# FourRotorV2_1.net
KiCad netlist of a schematic drawn in Altium Designer
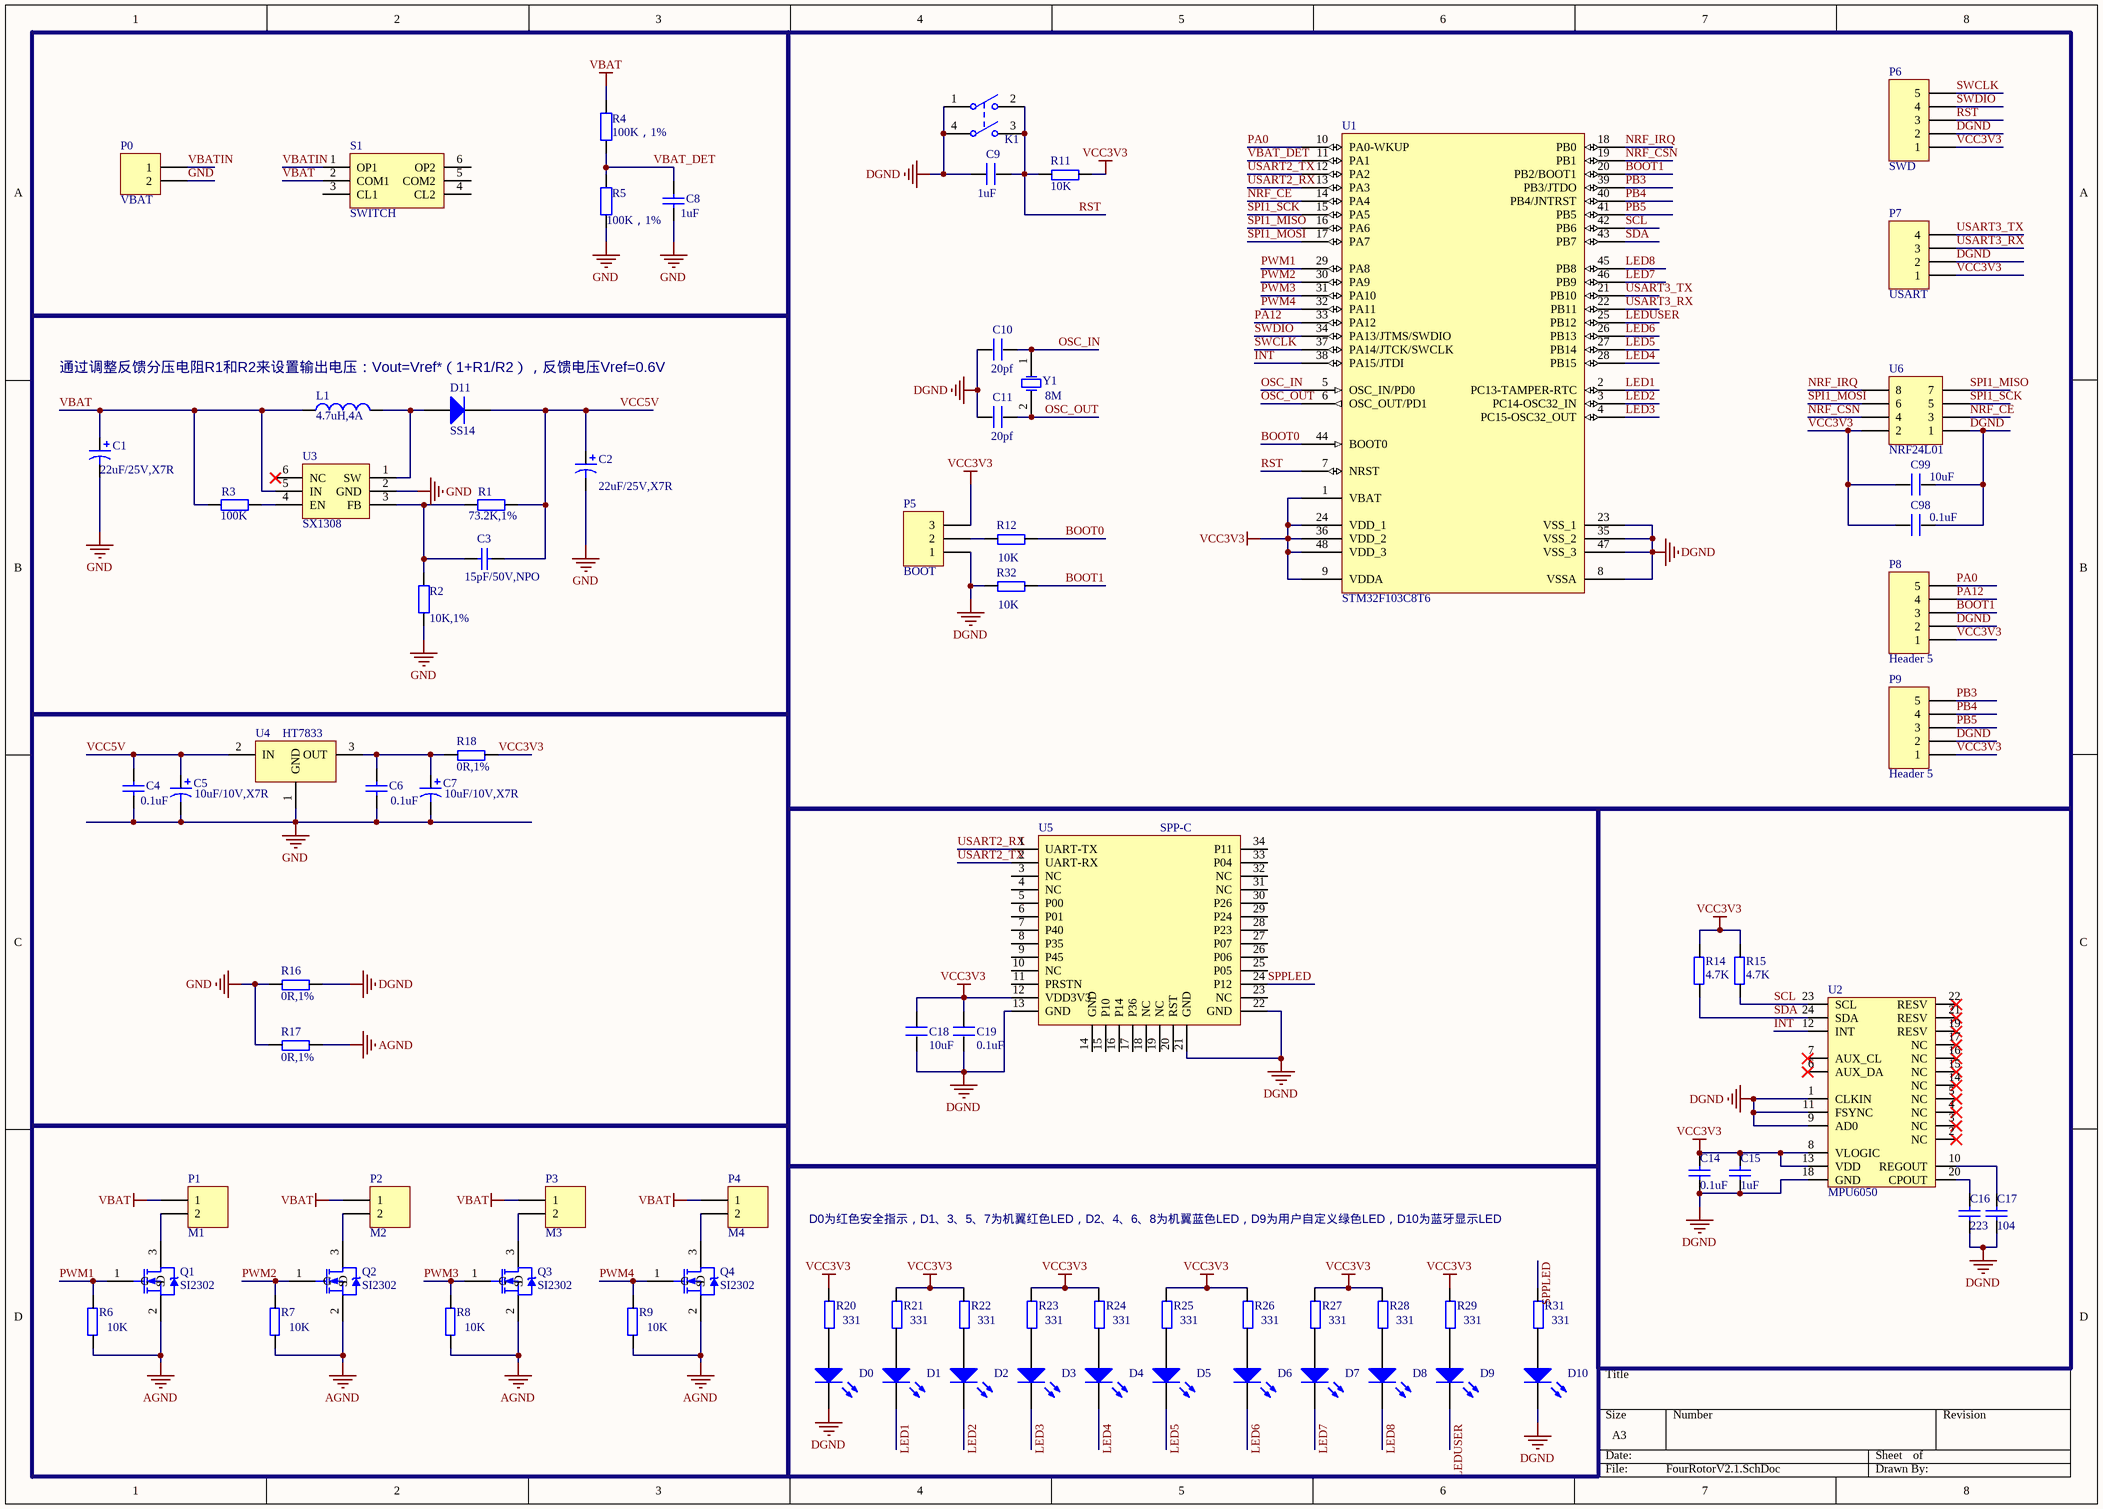
[diagram p0: FourRotorV2.1.SchDoc]

(export (version "E")
  (design (tool "Eeschema 10.0.6"))
  (components
    (comp (ref "C1")
      (value "22uF/25V,X7R")
      (footprint "LC-1206_C")
      (description "Polarized Capacitor (Radial)")
      (fields (field (name "Comment") "Cap Pol1") (field (name "PUBLISHER") "Altium Limited"))
      (libsource (lib "Miscellaneous Devices") (part "Cap Pol1"))
    )
    (comp (ref "C2")
      (value "22uF/25V,X7R")
      (footprint "LC-1206_C")
      (description "Polarized Capacitor (Radial)")
      (fields (field (name "Comment") "Cap Pol1") (field (name "PUBLISHER") "Altium Limited"))
      (libsource (lib "Miscellaneous Devices") (part "Cap Pol1"))
    )
    (comp (ref "C3")
      (value "15pF/50V,NPO")
      (footprint "LC-0603_C")
      (description "Capacitor")
      (fields (field (name "Comment") "Cap") (field (name "PUBLISHER") "Altium Limited"))
      (libsource (lib "Miscellaneous Devices") (part "Cap"))
    )
    (comp (ref "C4")
      (value "0.1uF")
      (footprint "LC-0603_C")
      (description "Capacitor")
      (fields (field (name "Comment") "Cap") (field (name "PUBLISHER") "Altium Limited"))
      (libsource (lib "Miscellaneous Devices") (part "Cap"))
    )
    (comp (ref "C5")
      (value "10uF/10V,X7R")
      (footprint "LC-1206_C")
      (description "Polarized Capacitor (Radial)")
      (fields (field (name "Comment") "Cap Pol1") (field (name "PUBLISHER") "Altium Limited"))
      (libsource (lib "Miscellaneous Devices") (part "Cap Pol1"))
    )
    (comp (ref "C6")
      (value "0.1uF")
      (footprint "LC-0603_C")
      (description "Capacitor")
      (fields (field (name "Comment") "Cap") (field (name "PUBLISHER") "Altium Limited"))
      (libsource (lib "Miscellaneous Devices") (part "Cap"))
    )
    (comp (ref "C7")
      (value "10uF/10V,X7R")
      (footprint "LC-1206_C")
      (description "Polarized Capacitor (Radial)")
      (fields (field (name "Comment") "Cap Pol1") (field (name "PUBLISHER") "Altium Limited"))
      (libsource (lib "Miscellaneous Devices") (part "Cap Pol1"))
    )
    (comp (ref "C8")
      (value "1uF")
      (footprint "LC-0603_C")
      (description "Capacitor")
      (fields (field (name "Comment") "Cap") (field (name "PUBLISHER") "Altium Limited"))
      (libsource (lib "Miscellaneous Devices") (part "Cap"))
    )
    (comp (ref "C9")
      (value "1uF")
      (footprint "LC-0603_C")
      (libsource (lib "Explorer STM32F407封装库") (part "C_1"))
    )
    (comp (ref "C10")
      (value "20pf")
      (footprint "LC-0603_C")
      (libsource (lib "Explorer STM32F407封装库") (part "C"))
    )
    (comp (ref "C11")
      (value "20pf")
      (footprint "LC-0603_C")
      (libsource (lib "Explorer STM32F407封装库") (part "C"))
    )
    (comp (ref "C14")
      (value "0.1uF")
      (footprint "LC-0603_C")
      (description "Capacitor")
      (fields (field (name "PUBLISHER") "Altium Limited"))
      (libsource (lib "Miscellaneous Devices") (part "Cap"))
    )
    (comp (ref "C15")
      (value "1uF")
      (footprint "LC-0603_C")
      (description "Capacitor")
      (fields (field (name "PUBLISHER") "Altium Limited"))
      (libsource (lib "Miscellaneous Devices") (part "Cap"))
    )
    (comp (ref "C16")
      (value "223")
      (footprint "LC-0603_C")
      (description "Capacitor")
      (fields (field (name "PUBLISHER") "Altium Limited"))
      (libsource (lib "Miscellaneous Devices") (part "Cap"))
    )
    (comp (ref "C17")
      (value "104")
      (footprint "LC-0603_C")
      (description "Capacitor")
      (fields (field (name "PUBLISHER") "Altium Limited"))
      (libsource (lib "Miscellaneous Devices") (part "Cap"))
    )
    (comp (ref "C18")
      (value "10uF")
      (footprint "LC-0805_C")
      (libsource (lib "Explorer STM32F407封装库") (part "C"))
    )
    (comp (ref "C19")
      (value "0.1uF")
      (footprint "LC-0603_C")
      (libsource (lib "Explorer STM32F407封装库") (part "C"))
    )
    (comp (ref "C98")
      (value "0.1uF")
      (footprint "LC-0603_C")
      (fields (field (name "Comment") "1uF"))
      (libsource (lib "Explorer STM32F407封装库") (part "C_1"))
    )
    (comp (ref "C99")
      (value "10uF")
      (footprint "LC-0805_C")
      (fields (field (name "Comment") "1uF"))
      (libsource (lib "Explorer STM32F407封装库") (part "C_1"))
    )
    (comp (ref "D0")
      (value "LED0")
      (footprint "LC-0805_LED_S1")
      (description "Typical INFRARED GaAs LED")
      (fields (field (name "PUBLISHER") "Altium Limited"))
      (libsource (lib "Miscellaneous Devices") (part "LED0"))
    )
    (comp (ref "D1")
      (value "LED0")
      (footprint "LC-0805_LED_S1")
      (description "Typical INFRARED GaAs LED")
      (fields (field (name "PUBLISHER") "Altium Limited"))
      (libsource (lib "Miscellaneous Devices") (part "LED0"))
    )
    (comp (ref "D2")
      (value "LED0")
      (footprint "LC-0805_LED_S1")
      (description "Typical INFRARED GaAs LED")
      (fields (field (name "PUBLISHER") "Altium Limited"))
      (libsource (lib "Miscellaneous Devices") (part "LED0"))
    )
    (comp (ref "D3")
      (value "LED0")
      (footprint "LC-0805_LED_S1")
      (description "Typical INFRARED GaAs LED")
      (fields (field (name "PUBLISHER") "Altium Limited"))
      (libsource (lib "Miscellaneous Devices") (part "LED0"))
    )
    (comp (ref "D4")
      (value "LED0")
      (footprint "LC-0805_LED_S1")
      (description "Typical INFRARED GaAs LED")
      (fields (field (name "PUBLISHER") "Altium Limited"))
      (libsource (lib "Miscellaneous Devices") (part "LED0"))
    )
    (comp (ref "D5")
      (value "LED0")
      (footprint "LC-0805_LED_S1")
      (description "Typical INFRARED GaAs LED")
      (fields (field (name "PUBLISHER") "Altium Limited"))
      (libsource (lib "Miscellaneous Devices") (part "LED0"))
    )
    (comp (ref "D6")
      (value "LED0")
      (footprint "LC-0805_LED_S1")
      (description "Typical INFRARED GaAs LED")
      (fields (field (name "PUBLISHER") "Altium Limited"))
      (libsource (lib "Miscellaneous Devices") (part "LED0"))
    )
    (comp (ref "D7")
      (value "LED0")
      (footprint "LC-0805_LED_S1")
      (description "Typical INFRARED GaAs LED")
      (fields (field (name "PUBLISHER") "Altium Limited"))
      (libsource (lib "Miscellaneous Devices") (part "LED0"))
    )
    (comp (ref "D8")
      (value "LED0")
      (footprint "LC-0805_LED_S1")
      (description "Typical INFRARED GaAs LED")
      (fields (field (name "PUBLISHER") "Altium Limited"))
      (libsource (lib "Miscellaneous Devices") (part "LED0"))
    )
    (comp (ref "D9")
      (value "LED0")
      (footprint "LC-0805_LED_S1")
      (description "Typical INFRARED GaAs LED")
      (fields (field (name "PUBLISHER") "Altium Limited"))
      (libsource (lib "Miscellaneous Devices") (part "LED0"))
    )
    (comp (ref "D10")
      (value "LED0")
      (footprint "LC-0805_LED_S1")
      (description "Typical INFRARED GaAs LED")
      (fields (field (name "PUBLISHER") "Altium Limited"))
      (libsource (lib "Miscellaneous Devices") (part "LED0"))
    )
    (comp (ref "D11")
      (value "SS14")
      (footprint "LC-DO-214AC")
      (description "1 Amp General Purpose Rectifier")
      (fields (field (name "PUBLISHER") "Altium Limited"))
      (libsource (lib "Miscellaneous Devices") (part "Diode 1N4001"))
    )
    (comp (ref "K1")
      (value "SW-DPST")
      (footprint "SWITCH2")
      (description "Double-Pole, Single-Throw Switch")
      (fields (field (name "PUBLISHER") "Altium Limited"))
      (libsource (lib "Miscellaneous Devices") (part "SW-DPST"))
    )
    (comp (ref "L1")
      (value "4.7uH,4A")
      (footprint "LC-1812_L")
      (description "Inductor")
      (fields (field (name "PUBLISHER") "Altium Limited"))
      (libsource (lib "Miscellaneous Devices") (part "Inductor"))
    )
    (comp (ref "P0")
      (value "VBAT")
      (footprint "HDR1X2")
      (description "Header, 2-Pin")
      (fields (field (name "PUBLISHER") "Altium Limited"))
      (libsource (lib "") (part "Header 2_1"))
    )
    (comp (ref "P1")
      (value "M1")
      (footprint "HDR1X2")
      (description "Header, 2-Pin")
      (fields (field (name "PUBLISHER") "Altium Limited"))
      (libsource (lib "Miscellaneous Connectors") (part "Header 2"))
    )
    (comp (ref "P2")
      (value "M2")
      (footprint "HDR1X2")
      (description "Header, 2-Pin")
      (fields (field (name "PUBLISHER") "Altium Limited"))
      (libsource (lib "Miscellaneous Connectors") (part "Header 2"))
    )
    (comp (ref "P3")
      (value "M3")
      (footprint "HDR1X2")
      (description "Header, 2-Pin")
      (fields (field (name "PUBLISHER") "Altium Limited"))
      (libsource (lib "Miscellaneous Connectors") (part "Header 2"))
    )
    (comp (ref "P4")
      (value "M4")
      (footprint "HDR1X2")
      (description "Header, 2-Pin")
      (fields (field (name "PUBLISHER") "Altium Limited"))
      (libsource (lib "Miscellaneous Connectors") (part "Header 2"))
    )
    (comp (ref "P5")
      (value "BOOT")
      (footprint "HDR1X3")
      (description "Header, 3-Pin")
      (fields (field (name "PUBLISHER") "Altium Limited"))
      (libsource (lib "Miscellaneous Connectors") (part "Header 3"))
    )
    (comp (ref "P6")
      (value "SWD")
      (footprint "HDR1X5")
      (description "Header, 5-Pin")
      (fields (field (name "PUBLISHER") "Altium Limited"))
      (libsource (lib "Miscellaneous Connectors") (part "Header 5"))
    )
    (comp (ref "P7")
      (value "USART")
      (footprint "HDR1X4")
      (description "Header, 4-Pin")
      (fields (field (name "PUBLISHER") "Altium Limited"))
      (libsource (lib "Miscellaneous Connectors") (part "Header 4"))
    )
    (comp (ref "P8")
      (value "Header 5")
      (footprint "HDR1X5")
      (description "Header, 5-Pin")
      (fields (field (name "PUBLISHER") "Altium Limited"))
      (libsource (lib "Miscellaneous Connectors") (part "Header 5"))
    )
    (comp (ref "P9")
      (value "Header 5")
      (footprint "HDR1X5")
      (description "Header, 5-Pin")
      (fields (field (name "PUBLISHER") "Altium Limited"))
      (libsource (lib "Miscellaneous Connectors") (part "Header 5"))
    )
    (comp (ref "Q1")
      (value "SI2302")
      (footprint "LC-SOT-23(SOT-23-3)")
      (description "N-Channel Power MOSFET")
      (fields (field (name "PUBLISHER") "Altium Limited"))
      (libsource (lib "Miscellaneous Devices") (part "NMOS-2"))
    )
    (comp (ref "Q2")
      (value "SI2302")
      (footprint "LC-SOT-23(SOT-23-3)")
      (description "N-Channel Power MOSFET")
      (fields (field (name "PUBLISHER") "Altium Limited"))
      (libsource (lib "Miscellaneous Devices") (part "NMOS-2"))
    )
    (comp (ref "Q3")
      (value "SI2302")
      (footprint "LC-SOT-23(SOT-23-3)")
      (description "N-Channel Power MOSFET")
      (fields (field (name "PUBLISHER") "Altium Limited"))
      (libsource (lib "Miscellaneous Devices") (part "NMOS-2"))
    )
    (comp (ref "Q4")
      (value "SI2302")
      (footprint "LC-SOT-23(SOT-23-3)")
      (description "N-Channel Power MOSFET")
      (fields (field (name "PUBLISHER") "Altium Limited"))
      (libsource (lib "Miscellaneous Devices") (part "NMOS-2"))
    )
    (comp (ref "R1")
      (value "73.2K,1%")
      (footprint "LC-0603_R")
      (description "Resistor")
      (fields (field (name "Comment") "Res2") (field (name "PUBLISHER") "Altium Limited"))
      (libsource (lib "Miscellaneous Devices") (part "Res2"))
    )
    (comp (ref "R2")
      (value "10K,1%")
      (footprint "LC-0603_R")
      (description "Resistor")
      (fields (field (name "Comment") "Res2") (field (name "PUBLISHER") "Altium Limited"))
      (libsource (lib "") (part "Res2_1"))
    )
    (comp (ref "R3")
      (value "100K")
      (footprint "LC-0603_R")
      (description "Resistor")
      (fields (field (name "Comment") "Res2") (field (name "PUBLISHER") "Altium Limited"))
      (libsource (lib "Miscellaneous Devices") (part "Res2"))
    )
    (comp (ref "R4")
      (value "100K，1%")
      (footprint "LC-0603_R")
      (description "Resistor")
      (fields (field (name "Comment") "Res2") (field (name "PUBLISHER") "Altium Limited"))
      (libsource (lib "") (part "Res2_1"))
    )
    (comp (ref "R5")
      (value "100K，1%")
      (footprint "LC-0603_R")
      (description "Resistor")
      (fields (field (name "Comment") "Res2") (field (name "PUBLISHER") "Altium Limited"))
      (libsource (lib "") (part "Res2_1"))
    )
    (comp (ref "R6")
      (value "10K")
      (footprint "LC-0603_R")
      (libsource (lib "Explorer STM32F407封装库") (part "R"))
    )
    (comp (ref "R7")
      (value "10K")
      (footprint "LC-0603_R")
      (libsource (lib "Explorer STM32F407封装库") (part "R"))
    )
    (comp (ref "R8")
      (value "10K")
      (footprint "LC-0603_R")
      (libsource (lib "Explorer STM32F407封装库") (part "R"))
    )
    (comp (ref "R9")
      (value "10K")
      (footprint "LC-0603_R")
      (libsource (lib "Explorer STM32F407封装库") (part "R"))
    )
    (comp (ref "R11")
      (value "10K")
      (footprint "LC-0603_R")
      (libsource (lib "Explorer STM32F407封装库") (part "R_1"))
    )
    (comp (ref "R12")
      (value "10K")
      (footprint "LC-0603_R")
      (libsource (lib "Explorer STM32F407封装库") (part "R"))
    )
    (comp (ref "R14")
      (value "4.7K")
      (footprint "LC-0603_R")
      (libsource (lib "Explorer STM32F407封装库") (part "R_1"))
    )
    (comp (ref "R15")
      (value "4.7K")
      (footprint "LC-0603_R")
      (libsource (lib "Explorer STM32F407封装库") (part "R_1"))
    )
    (comp (ref "R16")
      (value "0R,1%")
      (footprint "LC-0805_R")
      (libsource (lib "Explorer STM32F407封装库") (part "R"))
    )
    (comp (ref "R17")
      (value "0R,1%")
      (footprint "LC-0805_R")
      (libsource (lib "Explorer STM32F407封装库") (part "R"))
    )
    (comp (ref "R18")
      (value "0R,1%")
      (footprint "LC-0805_R")
      (libsource (lib "Explorer STM32F407封装库") (part "R"))
    )
    (comp (ref "R20")
      (value "331")
      (footprint "LC-0603_R")
      (libsource (lib "Explorer STM32F407封装库") (part "R_1"))
    )
    (comp (ref "R21")
      (value "331")
      (footprint "LC-0603_R")
      (libsource (lib "Explorer STM32F407封装库") (part "R_1"))
    )
    (comp (ref "R22")
      (value "331")
      (footprint "LC-0603_R")
      (libsource (lib "Explorer STM32F407封装库") (part "R_1"))
    )
    (comp (ref "R23")
      (value "331")
      (footprint "LC-0603_R")
      (libsource (lib "Explorer STM32F407封装库") (part "R_1"))
    )
    (comp (ref "R24")
      (value "331")
      (footprint "LC-0603_R")
      (libsource (lib "Explorer STM32F407封装库") (part "R_1"))
    )
    (comp (ref "R25")
      (value "331")
      (footprint "LC-0603_R")
      (libsource (lib "Explorer STM32F407封装库") (part "R_1"))
    )
    (comp (ref "R26")
      (value "331")
      (footprint "LC-0603_R")
      (libsource (lib "Explorer STM32F407封装库") (part "R_1"))
    )
    (comp (ref "R27")
      (value "331")
      (footprint "LC-0603_R")
      (libsource (lib "Explorer STM32F407封装库") (part "R_1"))
    )
    (comp (ref "R28")
      (value "331")
      (footprint "LC-0603_R")
      (libsource (lib "Explorer STM32F407封装库") (part "R_1"))
    )
    (comp (ref "R29")
      (value "331")
      (footprint "LC-0603_R")
      (libsource (lib "Explorer STM32F407封装库") (part "R_1"))
    )
    (comp (ref "R31")
      (value "331")
      (footprint "LC-0603_R")
      (libsource (lib "Explorer STM32F407封装库") (part "R_1"))
    )
    (comp (ref "R32")
      (value "10K")
      (footprint "LC-0603_R")
      (libsource (lib "Explorer STM32F407封装库") (part "R"))
    )
    (comp (ref "S1") (value "SWITCH") (footprint "SWITCH_6") (libsource (lib "mzwlib") (part "SWITCH")))
    (comp (ref "U1")
      (value "STM32F103C8T6")
      (footprint "LC-LQFP-48_7x7x05P")
      (description "STM32 ARM-based 32-bit MCU with 64 Kbytes Flash, 48-pin LQFP, Industrial Temperature")
      (fields (field (name "PUBLISHER") "Altium Limited"))
      (libsource (lib "ST Microcontroller 32-Bit STM32") (part "STM32F103C8T6"))
    )
    (comp (ref "U2")
      (value "MPU6050")
      (footprint "LC-QFN-24_4x4x05P")
      (description "9轴运动处理传感器")
      (libsource (lib "Explorer STM32F407封装库") (part "MPU6050"))
    )
    (comp (ref "U3") (value "SX1308") (footprint "LC-SOT-23-6") (libsource (lib "mzwlib") (part "SX1308")))
    (comp (ref "U4")
      (value "HT7833")
      (footprint "LC-SOT-89(SOT-89-3)")
      (libsource (lib "mzwlib") (part "HT7833"))
    )
    (comp (ref "U5") (value "SPP-C") (footprint "SPP-C") (libsource (lib "mzwlib") (part "SPP-C")))
    (comp (ref "U6")
      (value "NRF24L01")
      (footprint "LC-HDR2X4H")
      (description "Header, 4-Pin, Dual row, Right Angle")
      (fields (field (name "PUBLISHER") "Altium Limited"))
      (libsource (lib "Miscellaneous Connectors") (part "Header 4X2H"))
    )
    (comp (ref "Y1")
      (value "~")
      (footprint "LC-HC-49S")
      (description "Crystal Oscillator")
      (fields (field (name "ALTIUM_UNNAMED_1") "8M") (field (name "PUBLISHER") "Altium Limited"))
      (libsource (lib "Explorer STM32F407封装库") (part "XTAL"))
    )
  )
  (nets
    (net (code "1") (name "/BOOT0") (class "Default")
      (node (ref "R12") (pin "2") (pintype "passive"))
      (node (ref "U1") (pin "44") (pinfunction "BOOT0_44") (pintype "input"))
    )
    (net (code "2") (name "/BOOT1") (class "Default")
      (node (ref "P8") (pin "3") (pinfunction "3_3") (pintype "passive"))
      (node (ref "R32") (pin "2") (pintype "passive"))
      (node (ref "U1") (pin "20") (pinfunction "PB2/BOOT1_20") (pintype "bidirectional"))
    )
    (net (code "3") (name "/INT") (class "Default")
      (node (ref "U1") (pin "38") (pinfunction "PA15/JTDI_38") (pintype "bidirectional"))
      (node (ref "U2") (pin "12") (pinfunction "INT_12") (pintype "passive"))
    )
    (net (code "4") (name "/LED1") (class "Default")
      (node (ref "D1") (pin "2") (pinfunction "K_2") (pintype "passive"))
      (node (ref "U1") (pin "2") (pinfunction "PC13-TAMPER-RTC_2") (pintype "bidirectional"))
    )
    (net (code "5") (name "/LED2") (class "Default")
      (node (ref "D2") (pin "2") (pinfunction "K_2") (pintype "passive"))
      (node (ref "U1") (pin "3") (pinfunction "PC14-OSC32_IN_3") (pintype "bidirectional"))
    )
    (net (code "6") (name "/LED3") (class "Default")
      (node (ref "D3") (pin "2") (pinfunction "K_2") (pintype "passive"))
      (node (ref "U1") (pin "4") (pinfunction "PC15-OSC32_OUT_4") (pintype "bidirectional"))
    )
    (net (code "7") (name "/LED4") (class "Default")
      (node (ref "D4") (pin "2") (pinfunction "K_2") (pintype "passive"))
      (node (ref "U1") (pin "28") (pinfunction "PB15_28") (pintype "bidirectional"))
    )
    (net (code "8") (name "/LED5") (class "Default")
      (node (ref "D5") (pin "2") (pinfunction "K_2") (pintype "passive"))
      (node (ref "U1") (pin "27") (pinfunction "PB14_27") (pintype "bidirectional"))
    )
    (net (code "9") (name "/LED6") (class "Default")
      (node (ref "D6") (pin "2") (pinfunction "K_2") (pintype "passive"))
      (node (ref "U1") (pin "26") (pinfunction "PB13_26") (pintype "bidirectional"))
    )
    (net (code "10") (name "/LED7") (class "Default")
      (node (ref "D7") (pin "2") (pinfunction "K_2") (pintype "passive"))
      (node (ref "U1") (pin "46") (pinfunction "PB9_46") (pintype "bidirectional"))
    )
    (net (code "11") (name "/LED8") (class "Default")
      (node (ref "D8") (pin "2") (pinfunction "K_2") (pintype "passive"))
      (node (ref "U1") (pin "45") (pinfunction "PB8_45") (pintype "bidirectional"))
    )
    (net (code "12") (name "/LEDUSER") (class "Default")
      (node (ref "D9") (pin "2") (pinfunction "K_2") (pintype "passive"))
      (node (ref "U1") (pin "25") (pinfunction "PB12_25") (pintype "bidirectional"))
    )
    (net (code "13") (name "/NRF_CE") (class "Default")
      (node (ref "U1") (pin "14") (pinfunction "PA4_14") (pintype "bidirectional"))
      (node (ref "U6") (pin "3") (pinfunction "3_3") (pintype "passive"))
    )
    (net (code "14") (name "/NRF_CSN") (class "Default")
      (node (ref "U1") (pin "19") (pinfunction "PB1_19") (pintype "bidirectional"))
      (node (ref "U6") (pin "4") (pinfunction "4_4") (pintype "passive"))
    )
    (net (code "15") (name "/NRF_IRQ") (class "Default")
      (node (ref "U1") (pin "18") (pinfunction "PB0_18") (pintype "bidirectional"))
      (node (ref "U6") (pin "8") (pinfunction "8_8") (pintype "passive"))
    )
    (net (code "16") (name "/OSC_IN") (class "Default")
      (node (ref "C10") (pin "2") (pintype "passive"))
      (node (ref "U1") (pin "5") (pinfunction "OSC_IN/PD0_5") (pintype "input"))
      (node (ref "Y1") (pin "1") (pinfunction "OSC1_1") (pintype "passive"))
    )
    (net (code "17") (name "/OSC_OUT") (class "Default")
      (node (ref "C11") (pin "2") (pintype "passive"))
      (node (ref "U1") (pin "6") (pinfunction "OSC_OUT/PD1_6") (pintype "output"))
      (node (ref "Y1") (pin "2") (pinfunction "OSC2_2") (pintype "passive"))
    )
    (net (code "18") (name "/PA0") (class "Default")
      (node (ref "P8") (pin "5") (pinfunction "5_5") (pintype "passive"))
      (node (ref "U1") (pin "10") (pinfunction "PA0-WKUP_10") (pintype "bidirectional"))
    )
    (net (code "19") (name "/PA12") (class "Default")
      (node (ref "P8") (pin "4") (pinfunction "4_4") (pintype "passive"))
      (node (ref "U1") (pin "33") (pinfunction "PA12_33") (pintype "bidirectional"))
    )
    (net (code "20") (name "/PB3") (class "Default")
      (node (ref "P9") (pin "5") (pinfunction "5_5") (pintype "passive"))
      (node (ref "U1") (pin "39") (pinfunction "PB3/JTDO_39") (pintype "bidirectional"))
    )
    (net (code "21") (name "/PB4") (class "Default")
      (node (ref "P9") (pin "4") (pinfunction "4_4") (pintype "passive"))
      (node (ref "U1") (pin "40") (pinfunction "PB4/JNTRST_40") (pintype "bidirectional"))
    )
    (net (code "22") (name "/PB5") (class "Default")
      (node (ref "P9") (pin "3") (pinfunction "3_3") (pintype "passive"))
      (node (ref "U1") (pin "41") (pinfunction "PB5_41") (pintype "bidirectional"))
    )
    (net (code "23") (name "/PWM1") (class "Default")
      (node (ref "Q1") (pin "1") (pinfunction "G_1") (pintype "passive"))
      (node (ref "R6") (pin "1") (pintype "passive"))
      (node (ref "U1") (pin "29") (pinfunction "PA8_29") (pintype "bidirectional"))
    )
    (net (code "24") (name "/PWM2") (class "Default")
      (node (ref "Q2") (pin "1") (pinfunction "G_1") (pintype "passive"))
      (node (ref "R7") (pin "1") (pintype "passive"))
      (node (ref "U1") (pin "30") (pinfunction "PA9_30") (pintype "bidirectional"))
    )
    (net (code "25") (name "/PWM3") (class "Default")
      (node (ref "Q3") (pin "1") (pinfunction "G_1") (pintype "passive"))
      (node (ref "R8") (pin "1") (pintype "passive"))
      (node (ref "U1") (pin "31") (pinfunction "PA10_31") (pintype "bidirectional"))
    )
    (net (code "26") (name "/PWM4") (class "Default")
      (node (ref "Q4") (pin "1") (pinfunction "G_1") (pintype "passive"))
      (node (ref "R9") (pin "1") (pintype "passive"))
      (node (ref "U1") (pin "32") (pinfunction "PA11_32") (pintype "bidirectional"))
    )
    (net (code "27") (name "/RST") (class "Default")
      (node (ref "C9") (pin "2") (pintype "passive"))
      (node (ref "K1") (pin "2") (pinfunction "NO1_2") (pintype "passive"))
      (node (ref "K1") (pin "3") (pinfunction "NO2_3") (pintype "passive"))
      (node (ref "P6") (pin "3") (pinfunction "3_3") (pintype "passive"))
      (node (ref "R11") (pin "1") (pintype "passive"))
      (node (ref "U1") (pin "7") (pinfunction "NRST_7") (pintype "bidirectional"))
    )
    (net (code "28") (name "/SCL") (class "Default")
      (node (ref "R15") (pin "2") (pintype "passive"))
      (node (ref "U1") (pin "42") (pinfunction "PB6_42") (pintype "bidirectional"))
      (node (ref "U2") (pin "23") (pinfunction "SCL_23") (pintype "passive"))
    )
    (net (code "29") (name "/SDA") (class "Default")
      (node (ref "R14") (pin "2") (pintype "passive"))
      (node (ref "U1") (pin "43") (pinfunction "PB7_43") (pintype "bidirectional"))
      (node (ref "U2") (pin "24") (pinfunction "SDA_24") (pintype "passive"))
    )
    (net (code "30") (name "/SPI1_MISO") (class "Default")
      (node (ref "U1") (pin "16") (pinfunction "PA6_16") (pintype "bidirectional"))
      (node (ref "U6") (pin "7") (pinfunction "7_7") (pintype "passive"))
    )
    (net (code "31") (name "/SPI1_MOSI") (class "Default")
      (node (ref "U1") (pin "17") (pinfunction "PA7_17") (pintype "bidirectional"))
      (node (ref "U6") (pin "6") (pinfunction "6_6") (pintype "passive"))
    )
    (net (code "32") (name "/SPI1_SCK") (class "Default")
      (node (ref "U1") (pin "15") (pinfunction "PA5_15") (pintype "bidirectional"))
      (node (ref "U6") (pin "5") (pinfunction "5_5") (pintype "passive"))
    )
    (net (code "33") (name "/SPPLED") (class "Default")
      (node (ref "R31") (pin "2") (pintype "passive"))
      (node (ref "U5") (pin "24") (pinfunction "P12_24") (pintype "passive"))
    )
    (net (code "34") (name "/SWCLK") (class "Default")
      (node (ref "P6") (pin "5") (pinfunction "5_5") (pintype "passive"))
      (node (ref "U1") (pin "37") (pinfunction "PA14/JTCK/SWCLK_37") (pintype "bidirectional"))
    )
    (net (code "35") (name "/SWDIO") (class "Default")
      (node (ref "P6") (pin "4") (pinfunction "4_4") (pintype "passive"))
      (node (ref "U1") (pin "34") (pinfunction "PA13/JTMS/SWDIO_34") (pintype "bidirectional"))
    )
    (net (code "36") (name "/USART2_RX") (class "Default")
      (node (ref "U1") (pin "13") (pinfunction "PA3_13") (pintype "bidirectional"))
      (node (ref "U5") (pin "1") (pinfunction "UART-TX_1") (pintype "passive"))
    )
    (net (code "37") (name "/USART2_TX") (class "Default")
      (node (ref "U1") (pin "12") (pinfunction "PA2_12") (pintype "bidirectional"))
      (node (ref "U5") (pin "2") (pinfunction "UART-RX_2") (pintype "passive"))
    )
    (net (code "38") (name "/USART3_RX") (class "Default")
      (node (ref "P7") (pin "3") (pinfunction "3_3") (pintype "passive"))
      (node (ref "U1") (pin "22") (pinfunction "PB11_22") (pintype "bidirectional"))
    )
    (net (code "39") (name "/USART3_TX") (class "Default")
      (node (ref "P7") (pin "4") (pinfunction "4_4") (pintype "passive"))
      (node (ref "U1") (pin "21") (pinfunction "PB10_21") (pintype "bidirectional"))
    )
    (net (code "40") (name "/VBATIN") (class "Default")
      (node (ref "P0") (pin "1") (pinfunction "1_1") (pintype "passive"))
      (node (ref "S1") (pin "1") (pinfunction "OP1_1") (pintype "passive"))
    )
    (net (code "41") (name "/VBAT_DET") (class "Default")
      (node (ref "C8") (pin "2") (pinfunction "2_2") (pintype "passive"))
      (node (ref "R4") (pin "1") (pinfunction "1_1") (pintype "passive"))
      (node (ref "R5") (pin "2") (pinfunction "2_2") (pintype "passive"))
      (node (ref "U1") (pin "11") (pinfunction "PA1_11") (pintype "bidirectional"))
    )
    (net (code "42") (name "/VCC5V") (class "Default")
      (node (ref "C2") (pin "1") (pinfunction "1_1") (pintype "passive"))
      (node (ref "C3") (pin "2") (pinfunction "2_2") (pintype "passive"))
      (node (ref "C4") (pin "2") (pinfunction "2_2") (pintype "passive"))
      (node (ref "C5") (pin "1") (pinfunction "1_1") (pintype "passive"))
      (node (ref "D11") (pin "2") (pinfunction "K_2") (pintype "passive"))
      (node (ref "R1") (pin "2") (pinfunction "2_2") (pintype "passive"))
      (node (ref "U4") (pin "2") (pinfunction "IN_2") (pintype "passive"))
    )
    (net (code "43") (name "AGND") (class "Default")
      (node (ref "Q1") (pin "2") (pinfunction "S_2") (pintype "passive"))
      (node (ref "Q2") (pin "2") (pinfunction "S_2") (pintype "passive"))
      (node (ref "Q3") (pin "2") (pinfunction "S_2") (pintype "passive"))
      (node (ref "Q4") (pin "2") (pinfunction "S_2") (pintype "passive"))
      (node (ref "R17") (pin "2") (pintype "passive"))
      (node (ref "R6") (pin "2") (pintype "passive"))
      (node (ref "R7") (pin "2") (pintype "passive"))
      (node (ref "R8") (pin "2") (pintype "passive"))
      (node (ref "R9") (pin "2") (pintype "passive"))
    )
    (net (code "44") (name "DGND") (class "Default")
      (node (ref "C10") (pin "1") (pintype "passive"))
      (node (ref "C11") (pin "1") (pintype "passive"))
      (node (ref "C14") (pin "1") (pinfunction "1_1") (pintype "passive"))
      (node (ref "C15") (pin "1") (pinfunction "1_1") (pintype "passive"))
      (node (ref "C16") (pin "1") (pinfunction "1_1") (pintype "passive"))
      (node (ref "C17") (pin "1") (pinfunction "1_1") (pintype "passive"))
      (node (ref "C18") (pin "1") (pintype "passive"))
      (node (ref "C19") (pin "1") (pintype "passive"))
      (node (ref "C9") (pin "1") (pintype "passive"))
      (node (ref "C98") (pin "2") (pintype "passive"))
      (node (ref "C99") (pin "2") (pintype "passive"))
      (node (ref "D0") (pin "2") (pinfunction "K_2") (pintype "passive"))
      (node (ref "D10") (pin "2") (pinfunction "K_2") (pintype "passive"))
      (node (ref "K1") (pin "1") (pinfunction "COMMON1_1") (pintype "passive"))
      (node (ref "K1") (pin "4") (pinfunction "COMMON2_4") (pintype "passive"))
      (node (ref "P5") (pin "1") (pinfunction "1_1") (pintype "passive"))
      (node (ref "P6") (pin "2") (pinfunction "2_2") (pintype "passive"))
      (node (ref "P7") (pin "2") (pinfunction "2_2") (pintype "passive"))
      (node (ref "P8") (pin "2") (pinfunction "2_2") (pintype "passive"))
      (node (ref "P9") (pin "2") (pinfunction "2_2") (pintype "passive"))
      (node (ref "R16") (pin "2") (pintype "passive"))
      (node (ref "R32") (pin "1") (pintype "passive"))
      (node (ref "U1") (pin "23") (pinfunction "VSS_1_23") (pintype "power_in"))
      (node (ref "U1") (pin "35") (pinfunction "VSS_2_35") (pintype "power_in"))
      (node (ref "U1") (pin "47") (pinfunction "VSS_3_47") (pintype "power_in"))
      (node (ref "U1") (pin "8") (pinfunction "VSSA_8") (pintype "power_in"))
      (node (ref "U2") (pin "1") (pinfunction "CLKIN_1") (pintype "passive"))
      (node (ref "U2") (pin "11") (pinfunction "FSYNC_11") (pintype "passive"))
      (node (ref "U2") (pin "18") (pinfunction "GND_18") (pintype "passive"))
      (node (ref "U2") (pin "9") (pinfunction "AD0_9") (pintype "passive"))
      (node (ref "U5") (pin "13") (pinfunction "GND_13") (pintype "passive"))
      (node (ref "U5") (pin "21") (pinfunction "GND_21") (pintype "passive"))
      (node (ref "U5") (pin "22") (pinfunction "GND_22") (pintype "passive"))
      (node (ref "U6") (pin "1") (pinfunction "1_1") (pintype "passive"))
    )
    (net (code "45") (name "GND") (class "Default")
      (node (ref "C1") (pin "2") (pinfunction "2_2") (pintype "passive"))
      (node (ref "C2") (pin "2") (pinfunction "2_2") (pintype "passive"))
      (node (ref "C4") (pin "1") (pinfunction "1_1") (pintype "passive"))
      (node (ref "C5") (pin "2") (pinfunction "2_2") (pintype "passive"))
      (node (ref "C6") (pin "1") (pinfunction "1_1") (pintype "passive"))
      (node (ref "C7") (pin "2") (pinfunction "2_2") (pintype "passive"))
      (node (ref "C8") (pin "1") (pinfunction "1_1") (pintype "passive"))
      (node (ref "P0") (pin "2") (pinfunction "2_2") (pintype "passive"))
      (node (ref "R16") (pin "1") (pintype "passive"))
      (node (ref "R17") (pin "1") (pintype "passive"))
      (node (ref "R2") (pin "1") (pinfunction "1_1") (pintype "passive"))
      (node (ref "R5") (pin "1") (pinfunction "1_1") (pintype "passive"))
      (node (ref "U3") (pin "2") (pinfunction "GND_2") (pintype "passive"))
      (node (ref "U4") (pin "1") (pinfunction "GND_1") (pintype "passive"))
    )
    (net (code "46") (name "Net-(D0-A)") (class "Default")
      (node (ref "D0") (pin "1") (pinfunction "A_1") (pintype "passive"))
      (node (ref "R20") (pin "1") (pintype "passive"))
    )
    (net (code "47") (name "Net-(D1-A)") (class "Default")
      (node (ref "D1") (pin "1") (pinfunction "A_1") (pintype "passive"))
      (node (ref "R21") (pin "1") (pintype "passive"))
    )
    (net (code "48") (name "Net-(D2-A)") (class "Default")
      (node (ref "D2") (pin "1") (pinfunction "A_1") (pintype "passive"))
      (node (ref "R22") (pin "1") (pintype "passive"))
    )
    (net (code "49") (name "Net-(D3-A)") (class "Default")
      (node (ref "D3") (pin "1") (pinfunction "A_1") (pintype "passive"))
      (node (ref "R23") (pin "1") (pintype "passive"))
    )
    (net (code "50") (name "Net-(D4-A)") (class "Default")
      (node (ref "D4") (pin "1") (pinfunction "A_1") (pintype "passive"))
      (node (ref "R24") (pin "1") (pintype "passive"))
    )
    (net (code "51") (name "Net-(D5-A)") (class "Default")
      (node (ref "D5") (pin "1") (pinfunction "A_1") (pintype "passive"))
      (node (ref "R25") (pin "1") (pintype "passive"))
    )
    (net (code "52") (name "Net-(D6-A)") (class "Default")
      (node (ref "D6") (pin "1") (pinfunction "A_1") (pintype "passive"))
      (node (ref "R26") (pin "1") (pintype "passive"))
    )
    (net (code "53") (name "Net-(D7-A)") (class "Default")
      (node (ref "D7") (pin "1") (pinfunction "A_1") (pintype "passive"))
      (node (ref "R27") (pin "1") (pintype "passive"))
    )
    (net (code "54") (name "Net-(D8-A)") (class "Default")
      (node (ref "D8") (pin "1") (pinfunction "A_1") (pintype "passive"))
      (node (ref "R28") (pin "1") (pintype "passive"))
    )
    (net (code "55") (name "Net-(D9-A)") (class "Default")
      (node (ref "D9") (pin "1") (pinfunction "A_1") (pintype "passive"))
      (node (ref "R29") (pin "1") (pintype "passive"))
    )
    (net (code "56") (name "Net-(D10-A)") (class "Default")
      (node (ref "D10") (pin "1") (pinfunction "A_1") (pintype "passive"))
      (node (ref "R31") (pin "1") (pintype "passive"))
    )
    (net (code "57") (name "Net-(D11-A)") (class "Default")
      (node (ref "D11") (pin "1") (pinfunction "A_1") (pintype "passive"))
      (node (ref "L1") (pin "2") (pinfunction "2_2") (pintype "passive"))
      (node (ref "U3") (pin "1") (pinfunction "SW_1") (pintype "passive"))
    )
    (net (code "58") (name "Net-(P5-Pad2)") (class "Default")
      (node (ref "P5") (pin "2") (pinfunction "2_2") (pintype "passive"))
      (node (ref "R12") (pin "1") (pintype "passive"))
    )
    (net (code "59") (name "Net-(Q1-D)") (class "Default")
      (node (ref "P1") (pin "2") (pinfunction "2_2") (pintype "passive"))
      (node (ref "Q1") (pin "3") (pinfunction "D_3") (pintype "passive"))
    )
    (net (code "60") (name "Net-(Q2-D)") (class "Default")
      (node (ref "P2") (pin "2") (pinfunction "2_2") (pintype "passive"))
      (node (ref "Q2") (pin "3") (pinfunction "D_3") (pintype "passive"))
    )
    (net (code "61") (name "Net-(Q3-D)") (class "Default")
      (node (ref "P3") (pin "2") (pinfunction "2_2") (pintype "passive"))
      (node (ref "Q3") (pin "3") (pinfunction "D_3") (pintype "passive"))
    )
    (net (code "62") (name "Net-(Q4-D)") (class "Default")
      (node (ref "P4") (pin "2") (pinfunction "2_2") (pintype "passive"))
      (node (ref "Q4") (pin "3") (pinfunction "D_3") (pintype "passive"))
    )
    (net (code "63") (name "Net-(U2-CPOUT)") (class "Default")
      (node (ref "C16") (pin "2") (pinfunction "2_2") (pintype "passive"))
      (node (ref "U2") (pin "20") (pinfunction "CPOUT_20") (pintype "passive"))
    )
    (net (code "64") (name "Net-(U2-REGOUT)") (class "Default")
      (node (ref "C17") (pin "2") (pinfunction "2_2") (pintype "passive"))
      (node (ref "U2") (pin "10") (pinfunction "REGOUT_10") (pintype "passive"))
    )
    (net (code "65") (name "Net-(U3-EN)") (class "Default")
      (node (ref "R3") (pin "2") (pinfunction "2_2") (pintype "passive"))
      (node (ref "U3") (pin "4") (pinfunction "EN_4") (pintype "passive"))
    )
    (net (code "66") (name "Net-(U3-FB)") (class "Default")
      (node (ref "C3") (pin "1") (pinfunction "1_1") (pintype "passive"))
      (node (ref "R1") (pin "1") (pinfunction "1_1") (pintype "passive"))
      (node (ref "R2") (pin "2") (pinfunction "2_2") (pintype "passive"))
      (node (ref "U3") (pin "3") (pinfunction "FB_3") (pintype "passive"))
    )
    (net (code "67") (name "Net-(U4-OUT)") (class "Default")
      (node (ref "C6") (pin "2") (pinfunction "2_2") (pintype "passive"))
      (node (ref "C7") (pin "1") (pinfunction "1_1") (pintype "passive"))
      (node (ref "R18") (pin "1") (pintype "passive"))
      (node (ref "U4") (pin "3") (pinfunction "OUT_3") (pintype "passive"))
    )
    (net (code "68") (name "VBAT") (class "Default")
      (node (ref "C1") (pin "1") (pinfunction "1_1") (pintype "passive"))
      (node (ref "L1") (pin "1") (pinfunction "1_1") (pintype "passive"))
      (node (ref "P1") (pin "1") (pinfunction "1_1") (pintype "passive"))
      (node (ref "P2") (pin "1") (pinfunction "1_1") (pintype "passive"))
      (node (ref "P3") (pin "1") (pinfunction "1_1") (pintype "passive"))
      (node (ref "P4") (pin "1") (pinfunction "1_1") (pintype "passive"))
      (node (ref "R3") (pin "1") (pinfunction "1_1") (pintype "passive"))
      (node (ref "R4") (pin "2") (pinfunction "2_2") (pintype "passive"))
      (node (ref "S1") (pin "2") (pinfunction "COM1_2") (pintype "passive"))
      (node (ref "U3") (pin "5") (pinfunction "IN_5") (pintype "passive"))
    )
    (net (code "69") (name "VCC3V3") (class "Default")
      (node (ref "C14") (pin "2") (pinfunction "2_2") (pintype "passive"))
      (node (ref "C15") (pin "2") (pinfunction "2_2") (pintype "passive"))
      (node (ref "C18") (pin "2") (pintype "passive"))
      (node (ref "C19") (pin "2") (pintype "passive"))
      (node (ref "C98") (pin "1") (pintype "passive"))
      (node (ref "C99") (pin "1") (pintype "passive"))
      (node (ref "P5") (pin "3") (pinfunction "3_3") (pintype "passive"))
      (node (ref "P6") (pin "1") (pinfunction "1_1") (pintype "passive"))
      (node (ref "P7") (pin "1") (pinfunction "1_1") (pintype "passive"))
      (node (ref "P8") (pin "1") (pinfunction "1_1") (pintype "passive"))
      (node (ref "P9") (pin "1") (pinfunction "1_1") (pintype "passive"))
      (node (ref "R11") (pin "2") (pintype "passive"))
      (node (ref "R14") (pin "1") (pintype "passive"))
      (node (ref "R15") (pin "1") (pintype "passive"))
      (node (ref "R18") (pin "2") (pintype "passive"))
      (node (ref "R20") (pin "2") (pintype "passive"))
      (node (ref "R21") (pin "2") (pintype "passive"))
      (node (ref "R22") (pin "2") (pintype "passive"))
      (node (ref "R23") (pin "2") (pintype "passive"))
      (node (ref "R24") (pin "2") (pintype "passive"))
      (node (ref "R25") (pin "2") (pintype "passive"))
      (node (ref "R26") (pin "2") (pintype "passive"))
      (node (ref "R27") (pin "2") (pintype "passive"))
      (node (ref "R28") (pin "2") (pintype "passive"))
      (node (ref "R29") (pin "2") (pintype "passive"))
      (node (ref "U1") (pin "1") (pinfunction "VBAT_1") (pintype "power_in"))
      (node (ref "U1") (pin "24") (pinfunction "VDD_1_24") (pintype "power_in"))
      (node (ref "U1") (pin "36") (pinfunction "VDD_2_36") (pintype "power_in"))
      (node (ref "U1") (pin "48") (pinfunction "VDD_3_48") (pintype "power_in"))
      (node (ref "U1") (pin "9") (pinfunction "VDDA_9") (pintype "power_in"))
      (node (ref "U2") (pin "13") (pinfunction "VDD_13") (pintype "passive"))
      (node (ref "U2") (pin "8") (pinfunction "VLOGIC_8") (pintype "passive"))
      (node (ref "U5") (pin "12") (pinfunction "VDD3V3_12") (pintype "passive"))
      (node (ref "U6") (pin "2") (pinfunction "2_2") (pintype "passive"))
    )
    (net (code "70") (name "unconnected-(S1-CL1-Pad3)") (class "Default")
      (node (ref "S1") (pin "3") (pinfunction "CL1_3") (pintype "passive"))
    )
    (net (code "71") (name "unconnected-(S1-CL2-Pad4)") (class "Default")
      (node (ref "S1") (pin "4") (pinfunction "CL2_4") (pintype "passive"))
    )
    (net (code "72") (name "unconnected-(S1-COM2-Pad5)") (class "Default")
      (node (ref "S1") (pin "5") (pinfunction "COM2_5") (pintype "passive"))
    )
    (net (code "73") (name "unconnected-(S1-OP2-Pad6)") (class "Default")
      (node (ref "S1") (pin "6") (pinfunction "OP2_6") (pintype "passive"))
    )
    (net (code "74") (name "unconnected-(U2-AUX_CL-Pad7)") (class "Default")
      (node (ref "U2") (pin "7") (pinfunction "AUX_CL_7") (pintype "passive+no_connect"))
    )
    (net (code "75") (name "unconnected-(U2-AUX_DA-Pad6)") (class "Default")
      (node (ref "U2") (pin "6") (pinfunction "AUX_DA_6") (pintype "passive+no_connect"))
    )
    (net (code "76") (name "unconnected-(U2-NC-Pad2)") (class "Default")
      (node (ref "U2") (pin "2") (pinfunction "NC_2") (pintype "passive+no_connect"))
    )
    (net (code "77") (name "unconnected-(U2-NC-Pad3)") (class "Default")
      (node (ref "U2") (pin "3") (pinfunction "NC_3") (pintype "passive+no_connect"))
    )
    (net (code "78") (name "unconnected-(U2-NC-Pad4)") (class "Default")
      (node (ref "U2") (pin "4") (pinfunction "NC_4") (pintype "passive+no_connect"))
    )
    (net (code "79") (name "unconnected-(U2-NC-Pad5)") (class "Default")
      (node (ref "U2") (pin "5") (pinfunction "NC_5") (pintype "passive+no_connect"))
    )
    (net (code "80") (name "unconnected-(U2-NC-Pad14)") (class "Default")
      (node (ref "U2") (pin "14") (pinfunction "NC_14") (pintype "passive+no_connect"))
    )
    (net (code "81") (name "unconnected-(U2-NC-Pad15)") (class "Default")
      (node (ref "U2") (pin "15") (pinfunction "NC_15") (pintype "passive+no_connect"))
    )
    (net (code "82") (name "unconnected-(U2-NC-Pad16)") (class "Default")
      (node (ref "U2") (pin "16") (pinfunction "NC_16") (pintype "passive+no_connect"))
    )
    (net (code "83") (name "unconnected-(U2-NC-Pad17)") (class "Default")
      (node (ref "U2") (pin "17") (pinfunction "NC_17") (pintype "passive+no_connect"))
    )
    (net (code "84") (name "unconnected-(U2-RESV-Pad19)") (class "Default")
      (node (ref "U2") (pin "19") (pinfunction "RESV_19") (pintype "passive+no_connect"))
    )
    (net (code "85") (name "unconnected-(U2-RESV-Pad21)") (class "Default")
      (node (ref "U2") (pin "21") (pinfunction "RESV_21") (pintype "passive+no_connect"))
    )
    (net (code "86") (name "unconnected-(U2-RESV-Pad22)") (class "Default")
      (node (ref "U2") (pin "22") (pinfunction "RESV_22") (pintype "passive+no_connect"))
    )
    (net (code "87") (name "unconnected-(U3-NC-Pad6)") (class "Default")
      (node (ref "U3") (pin "6") (pinfunction "NC_6") (pintype "passive+no_connect"))
    )
    (net (code "88") (name "unconnected-(U5-GND-Pad14)") (class "Default")
      (node (ref "U5") (pin "14") (pinfunction "GND_14") (pintype "passive"))
    )
    (net (code "89") (name "unconnected-(U5-NC-Pad3)") (class "Default")
      (node (ref "U5") (pin "3") (pinfunction "NC_3") (pintype "passive"))
    )
    (net (code "90") (name "unconnected-(U5-NC-Pad4)") (class "Default")
      (node (ref "U5") (pin "4") (pinfunction "NC_4") (pintype "passive"))
    )
    (net (code "91") (name "unconnected-(U5-NC-Pad10)") (class "Default")
      (node (ref "U5") (pin "10") (pinfunction "NC_10") (pintype "passive"))
    )
    (net (code "92") (name "unconnected-(U5-NC-Pad18)") (class "Default")
      (node (ref "U5") (pin "18") (pinfunction "NC_18") (pintype "passive"))
    )
    (net (code "93") (name "unconnected-(U5-NC-Pad19)") (class "Default")
      (node (ref "U5") (pin "19") (pinfunction "NC_19") (pintype "passive"))
    )
    (net (code "94") (name "unconnected-(U5-NC-Pad23)") (class "Default")
      (node (ref "U5") (pin "23") (pinfunction "NC_23") (pintype "passive"))
    )
    (net (code "95") (name "unconnected-(U5-NC-Pad31)") (class "Default")
      (node (ref "U5") (pin "31") (pinfunction "NC_31") (pintype "passive"))
    )
    (net (code "96") (name "unconnected-(U5-NC-Pad32)") (class "Default")
      (node (ref "U5") (pin "32") (pinfunction "NC_32") (pintype "passive"))
    )
    (net (code "97") (name "unconnected-(U5-P00-Pad5)") (class "Default")
      (node (ref "U5") (pin "5") (pinfunction "P00_5") (pintype "passive"))
    )
    (net (code "98") (name "unconnected-(U5-P01-Pad6)") (class "Default")
      (node (ref "U5") (pin "6") (pinfunction "P01_6") (pintype "passive"))
    )
    (net (code "99") (name "unconnected-(U5-P04-Pad33)") (class "Default")
      (node (ref "U5") (pin "33") (pinfunction "P04_33") (pintype "passive"))
    )
    (net (code "100") (name "unconnected-(U5-P05-Pad25)") (class "Default")
      (node (ref "U5") (pin "25") (pinfunction "P05_25") (pintype "passive"))
    )
    (net (code "101") (name "unconnected-(U5-P06-Pad26)") (class "Default")
      (node (ref "U5") (pin "26") (pinfunction "P06_26") (pintype "passive"))
    )
    (net (code "102") (name "unconnected-(U5-P07-Pad27)") (class "Default")
      (node (ref "U5") (pin "27") (pinfunction "P07_27") (pintype "passive"))
    )
    (net (code "103") (name "unconnected-(U5-P10-Pad15)") (class "Default")
      (node (ref "U5") (pin "15") (pinfunction "P10_15") (pintype "passive"))
    )
    (net (code "104") (name "unconnected-(U5-P11-Pad34)") (class "Default")
      (node (ref "U5") (pin "34") (pinfunction "P11_34") (pintype "passive"))
    )
    (net (code "105") (name "unconnected-(U5-P14-Pad16)") (class "Default")
      (node (ref "U5") (pin "16") (pinfunction "P14_16") (pintype "passive"))
    )
    (net (code "106") (name "unconnected-(U5-P23-Pad28)") (class "Default")
      (node (ref "U5") (pin "28") (pinfunction "P23_28") (pintype "passive"))
    )
    (net (code "107") (name "unconnected-(U5-P24-Pad29)") (class "Default")
      (node (ref "U5") (pin "29") (pinfunction "P24_29") (pintype "passive"))
    )
    (net (code "108") (name "unconnected-(U5-P26-Pad30)") (class "Default")
      (node (ref "U5") (pin "30") (pinfunction "P26_30") (pintype "passive"))
    )
    (net (code "109") (name "unconnected-(U5-P35-Pad8)") (class "Default")
      (node (ref "U5") (pin "8") (pinfunction "P35_8") (pintype "passive"))
    )
    (net (code "110") (name "unconnected-(U5-P36-Pad17)") (class "Default")
      (node (ref "U5") (pin "17") (pinfunction "P36_17") (pintype "passive"))
    )
    (net (code "111") (name "unconnected-(U5-P40-Pad7)") (class "Default")
      (node (ref "U5") (pin "7") (pinfunction "P40_7") (pintype "passive"))
    )
    (net (code "112") (name "unconnected-(U5-P45-Pad9)") (class "Default")
      (node (ref "U5") (pin "9") (pinfunction "P45_9") (pintype "passive"))
    )
    (net (code "113") (name "unconnected-(U5-PRSTN-Pad11)") (class "Default")
      (node (ref "U5") (pin "11") (pinfunction "PRSTN_11") (pintype "passive"))
    )
    (net (code "114") (name "unconnected-(U5-RST-Pad20)") (class "Default")
      (node (ref "U5") (pin "20") (pinfunction "RST_20") (pintype "passive"))
    )
  )
)
